# Microcontroller.net
KiCad netlist of a schematic drawn in Altium Designer
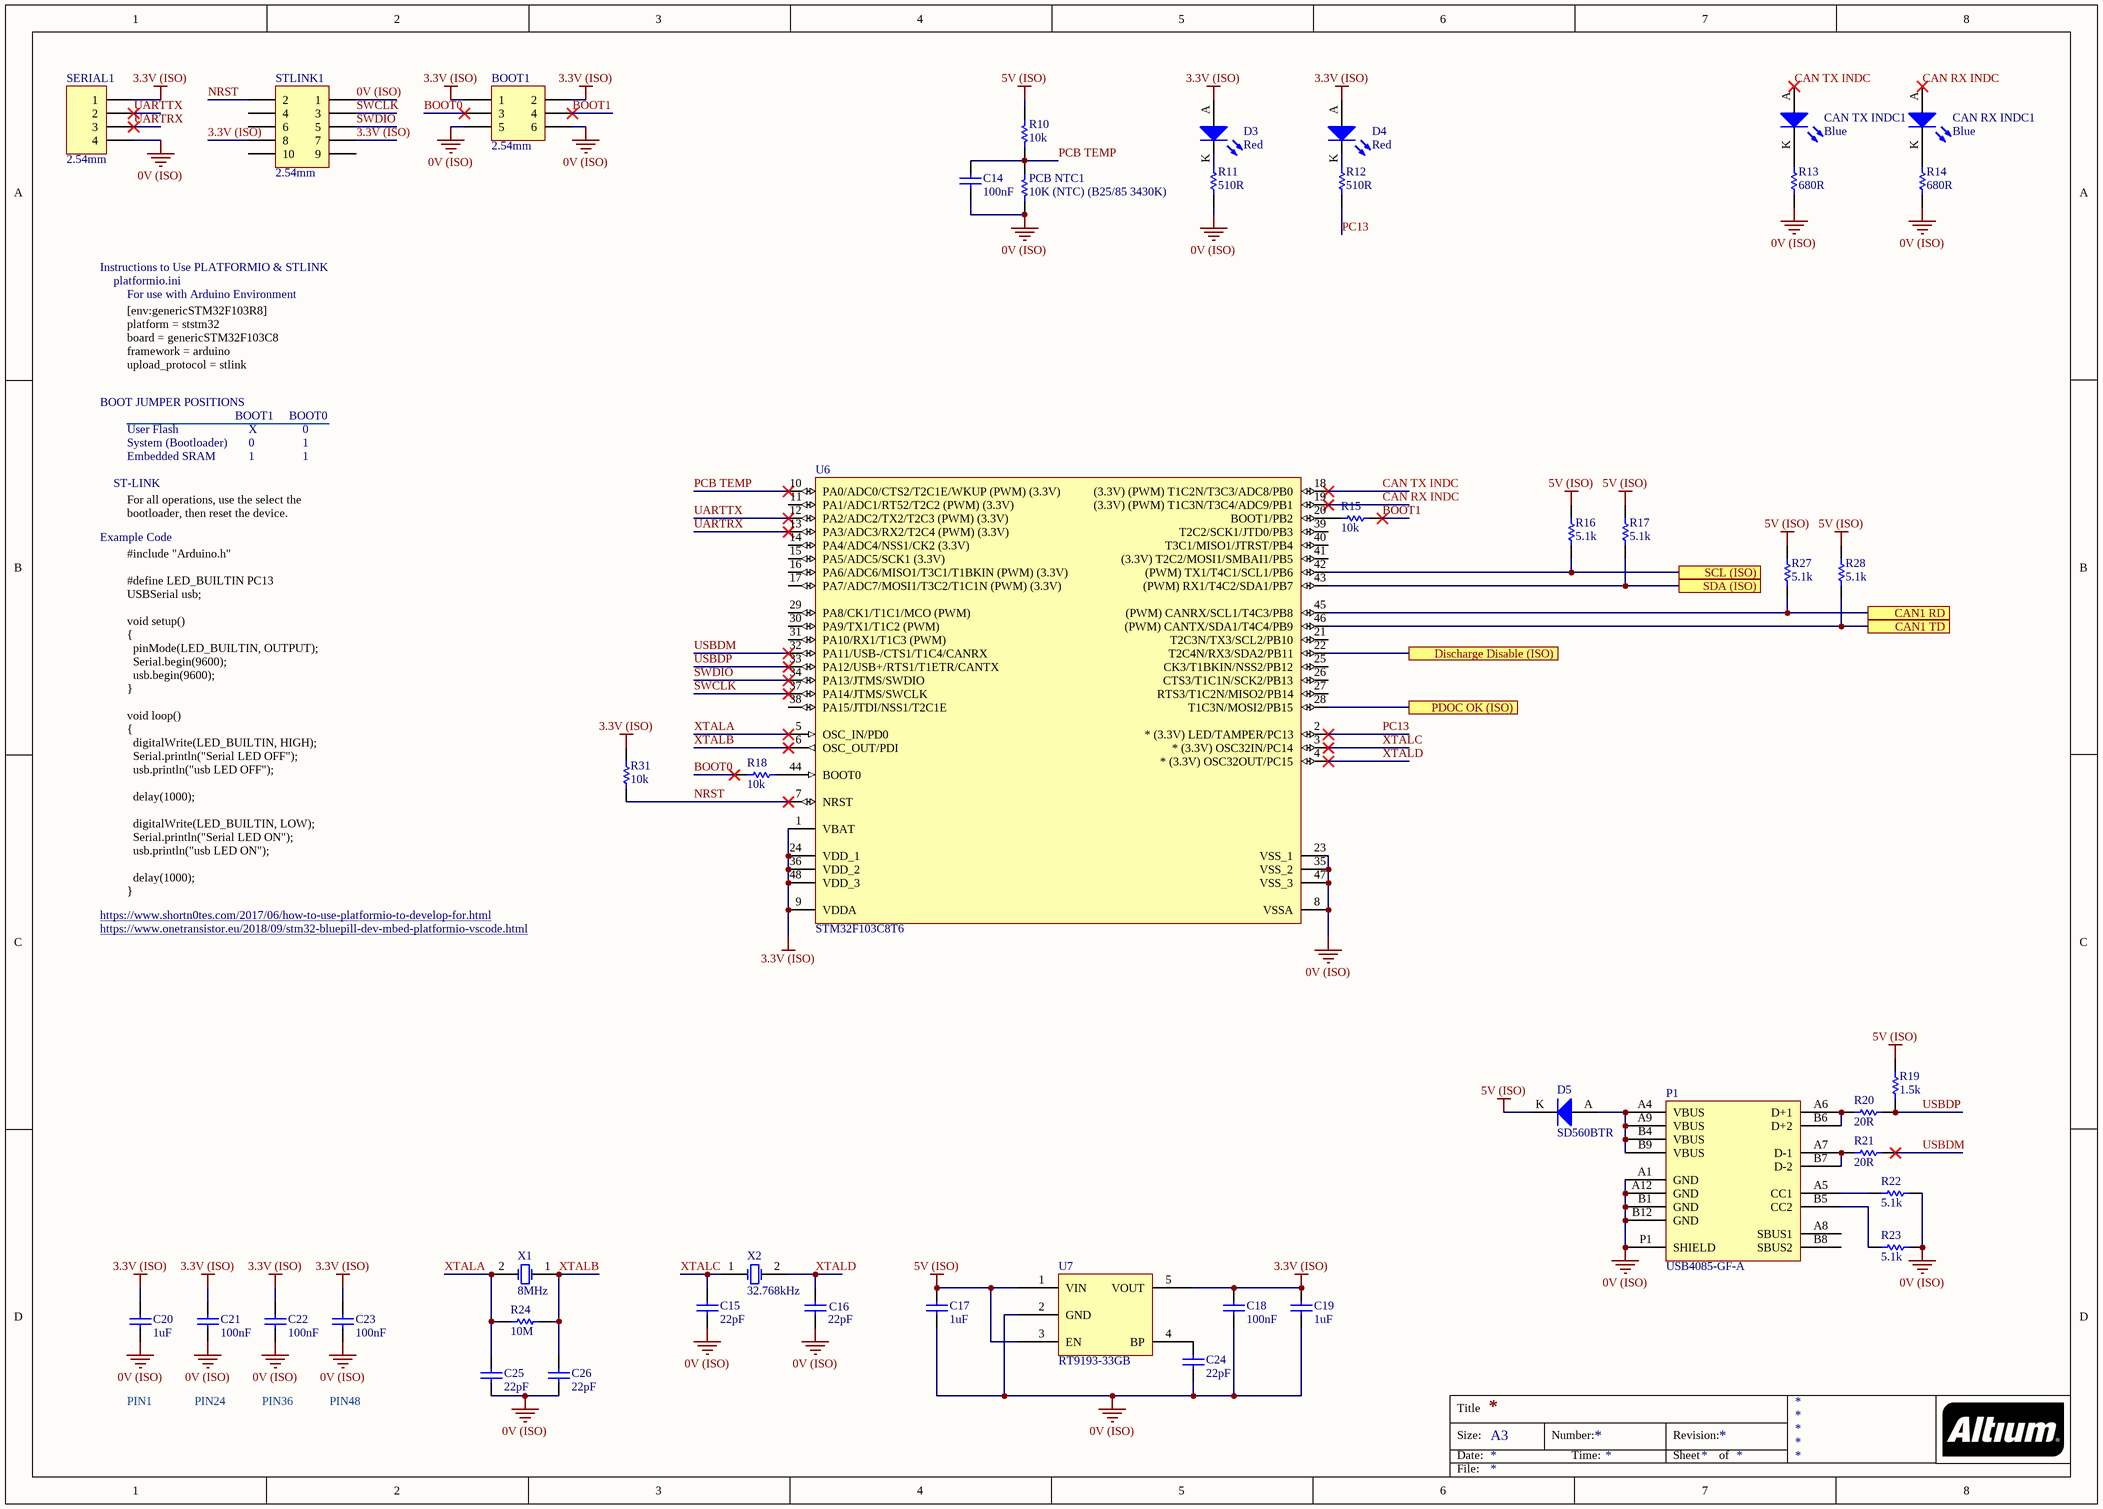
[diagram p0: Microcontroller.SchDoc]

(export (version "E")
  (design (tool "Eeschema 10.0.6"))
  (components
    (comp (ref "BOOT1")
      (value "2.54mm")
      (footprint "TH 2.54mm Header 2x3")
      (fields (field (name "PART NUMBER") "TH 2.54mm Header 2x3") (field (name "CONTACT") "NA"))
      (libsource (lib "ts_20-standard-connectors") (part "Header 2x3"))
    )
    (comp (ref "C14")
      (value "100nF")
      (footprint "0805")
      (fields
        (field (name "PART NUMBER") "GCM21BR71H104KA37L")
        (field (name "TOLERANCE") "±10%")
        (field (name "MANUFACTURER") "muRata")
      )
      (libsource (lib "ts_20-standard-library") (part "Capacitor"))
    )
    (comp (ref "C15")
      (value "22pF")
      (footprint "0805")
      (fields
        (field (name "PART NUMBER") "GRM21A5C2E220JW01D")
        (field (name "TOLERANCE") "±5%")
        (field (name "MANUFACTURER") "muRata")
      )
      (libsource (lib "ts_20-standard-library") (part "Capacitor"))
    )
    (comp (ref "C16")
      (value "22pF")
      (footprint "0805")
      (fields
        (field (name "PART NUMBER") "GRM21A5C2E220JW01D")
        (field (name "TOLERANCE") "±5%")
        (field (name "MANUFACTURER") "muRata")
      )
      (libsource (lib "ts_20-standard-library") (part "Capacitor"))
    )
    (comp (ref "C17")
      (value "1uF")
      (footprint "0805")
      (fields
        (field (name "PART NUMBER") "AC0805KKX7R8BB105")
        (field (name "TOLERANCE") "10%")
        (field (name "MANUFACTURER") "YAGEO")
      )
      (libsource (lib "ts_20-standard-library") (part "Capacitor"))
    )
    (comp (ref "C18")
      (value "100nF")
      (footprint "0805")
      (fields
        (field (name "PART NUMBER") "GCM21BR71H104KA37L")
        (field (name "TOLERANCE") "±10%")
        (field (name "MANUFACTURER") "muRata")
      )
      (libsource (lib "ts_20-standard-library") (part "Capacitor"))
    )
    (comp (ref "C19")
      (value "1uF")
      (footprint "0805")
      (fields
        (field (name "PART NUMBER") "AC0805KKX7R8BB105")
        (field (name "TOLERANCE") "10%")
        (field (name "MANUFACTURER") "YAGEO")
      )
      (libsource (lib "ts_20-standard-library") (part "Capacitor"))
    )
    (comp (ref "C20")
      (value "1uF")
      (footprint "0805")
      (fields
        (field (name "PART NUMBER") "AC0805KKX7R8BB105")
        (field (name "TOLERANCE") "10%")
        (field (name "MANUFACTURER") "YAGEO")
      )
      (libsource (lib "ts_20-standard-library") (part "Capacitor"))
    )
    (comp (ref "C21")
      (value "100nF")
      (footprint "0805")
      (fields
        (field (name "PART NUMBER") "GCM21BR71H104KA37L")
        (field (name "TOLERANCE") "±10%")
        (field (name "MANUFACTURER") "muRata")
      )
      (libsource (lib "ts_20-standard-library") (part "Capacitor"))
    )
    (comp (ref "C22")
      (value "100nF")
      (footprint "0805")
      (fields
        (field (name "PART NUMBER") "GCM21BR71H104KA37L")
        (field (name "TOLERANCE") "±10%")
        (field (name "MANUFACTURER") "muRata")
      )
      (libsource (lib "ts_20-standard-library") (part "Capacitor"))
    )
    (comp (ref "C23")
      (value "100nF")
      (footprint "0805")
      (fields
        (field (name "PART NUMBER") "GCM21BR71H104KA37L")
        (field (name "TOLERANCE") "±10%")
        (field (name "MANUFACTURER") "muRata")
      )
      (libsource (lib "ts_20-standard-library") (part "Capacitor"))
    )
    (comp (ref "C24")
      (value "22pF")
      (footprint "0805")
      (fields
        (field (name "PART NUMBER") "GRM21A5C2E220JW01D")
        (field (name "TOLERANCE") "±5%")
        (field (name "MANUFACTURER") "muRata")
      )
      (libsource (lib "ts_20-standard-library") (part "Capacitor"))
    )
    (comp (ref "C25")
      (value "22pF")
      (footprint "0805")
      (fields
        (field (name "PART NUMBER") "GRM21A5C2E220JW01D")
        (field (name "TOLERANCE") "±5%")
        (field (name "MANUFACTURER") "muRata")
      )
      (libsource (lib "ts_20-standard-library") (part "Capacitor"))
    )
    (comp (ref "C26")
      (value "22pF")
      (footprint "0805")
      (fields
        (field (name "PART NUMBER") "GRM21A5C2E220JW01D")
        (field (name "TOLERANCE") "±5%")
        (field (name "MANUFACTURER") "muRata")
      )
      (libsource (lib "ts_20-standard-library") (part "Capacitor"))
    )
    (comp (ref "CAN RX INDC1")
      (value "Blue")
      (footprint "0805 LED")
      (description "LED BLUE CLEAR 2012 SMD")
      (fields
        (field (name "PART NUMBER") "SML-MN2BCTT86C")
        (field (name "MANUFACTURER") "ROHM Semiconductor")
      )
      (libsource (lib "ts_20-standard-library") (part "LED"))
    )
    (comp (ref "CAN TX INDC1")
      (value "Blue")
      (footprint "0805 LED")
      (description "LED BLUE CLEAR 2012 SMD")
      (fields
        (field (name "PART NUMBER") "SML-MN2BCTT86C")
        (field (name "MANUFACTURER") "ROHM Semiconductor")
      )
      (libsource (lib "ts_20-standard-library") (part "LED"))
    )
    (comp (ref "D3")
      (value "Red")
      (footprint "0805 LED")
      (description "Red LED Indication - Discrete 1.75V 0805 (2012 Metric)")
      (fields (field (name "MANUFACTURER") "ROHM Semiconductor") (field (name "PART NUMBER") "SML-210LTT86"))
      (libsource (lib "ts_20-standard-library") (part "LED"))
    )
    (comp (ref "D4")
      (value "Red")
      (footprint "0805 LED")
      (description "Red LED Indication - Discrete 1.75V 0805 (2012 Metric)")
      (fields (field (name "MANUFACTURER") "ROHM Semiconductor") (field (name "PART NUMBER") "SML-210LTT86"))
      (libsource (lib "ts_20-standard-library") (part "LED"))
    )
    (comp (ref "D5")
      (value "SD560BTR")
      (footprint "SMB Diode")
      (description "1.2V_F 600V 5A SMB")
      (fields
        (field (name "MANUFACTURER") "SMC Diode Solutions")
        (field (name "DIGIKEY PART NUMBER") "1655-1530-2-ND")
      )
      (libsource (lib "ts_20-standard-library") (part "Diode"))
    )
    (comp (ref "P1")
      (value "USB4085-GF-A")
      (footprint "USB4085-GF-A")
      (description "USB - C (Type - C) USB 2.0 Receptacle Connector 16 Position Through Hole, Right Angle")
      (fields (field (name "DIGIKEY PART NUMBER") "2073-USB4085-GF-ACT-ND"))
      (libsource (lib "ts_20-standard-connectors") (part "USB4085-GF-A"))
    )
    (comp (ref "PCB NTC1")
      (value "10K (NTC) (B25/85 3430K)")
      (footprint "0805")
      (fields
        (field (name "PART NUMBER") "NTCS0805E3103FLT")
        (field (name "MANUFACTURER") "Vishay Beyschlag")
        (field (name "TOLERANCE") "0.01")
      )
      (libsource (lib "ts_20-standard-library") (part "Resistor"))
    )
    (comp (ref "R10")
      (value "10k")
      (footprint "0805")
      (fields
        (field (name "PART NUMBER") "RC0805FR0710KL")
        (field (name "MANUFACTURER") "YAGEO")
        (field (name "TOLERANCE") "0.01")
      )
      (libsource (lib "ts_20-standard-library") (part "Resistor"))
    )
    (comp (ref "R11")
      (value "510R")
      (footprint "0805")
      (fields
        (field (name "MANUFACTURER") "YAGEO")
        (field (name "PART NUMBER") "RC0805FR07510RL")
        (field (name "TOLERANCE") "0.01")
      )
      (libsource (lib "ts_20-standard-library") (part "Resistor"))
    )
    (comp (ref "R12")
      (value "510R")
      (footprint "0805")
      (fields
        (field (name "MANUFACTURER") "YAGEO")
        (field (name "PART NUMBER") "RC0805FR07510RL")
        (field (name "TOLERANCE") "0.01")
      )
      (libsource (lib "ts_20-standard-library") (part "Resistor"))
    )
    (comp (ref "R13")
      (value "680R")
      (footprint "0805")
      (fields
        (field (name "PART NUMBER") "RC0805FR07680RL")
        (field (name "MANUFACTURER") "YAGEO")
        (field (name "TOLERANCE") "0.01")
      )
      (libsource (lib "ts_20-standard-library") (part "Resistor"))
    )
    (comp (ref "R14")
      (value "680R")
      (footprint "0805")
      (fields
        (field (name "PART NUMBER") "RC0805FR07680RL")
        (field (name "MANUFACTURER") "YAGEO")
        (field (name "TOLERANCE") "0.01")
      )
      (libsource (lib "ts_20-standard-library") (part "Resistor"))
    )
    (comp (ref "R15")
      (value "10k")
      (footprint "0805")
      (fields
        (field (name "PART NUMBER") "RC0805FR0710KL")
        (field (name "MANUFACTURER") "YAGEO")
        (field (name "TOLERANCE") "0.01")
      )
      (libsource (lib "ts_20-standard-library") (part "Resistor"))
    )
    (comp (ref "R16")
      (value "5.1k")
      (footprint "0805")
      (fields
        (field (name "PART NUMBER") "RC0805FR075K1L")
        (field (name "MANUFACTURER") "YAGEO")
        (field (name "TOLERANCE") "0.01")
      )
      (libsource (lib "ts_20-standard-library") (part "Resistor"))
    )
    (comp (ref "R17")
      (value "5.1k")
      (footprint "0805")
      (fields
        (field (name "PART NUMBER") "RC0805FR075K1L")
        (field (name "MANUFACTURER") "YAGEO")
        (field (name "TOLERANCE") "0.01")
      )
      (libsource (lib "ts_20-standard-library") (part "Resistor"))
    )
    (comp (ref "R18")
      (value "10k")
      (footprint "0805")
      (fields
        (field (name "PART NUMBER") "RC0805FR0710KL")
        (field (name "MANUFACTURER") "YAGEO")
        (field (name "TOLERANCE") "0.01")
      )
      (libsource (lib "ts_20-standard-library") (part "Resistor"))
    )
    (comp (ref "R19")
      (value "1.5k")
      (footprint "0805")
      (fields
        (field (name "PART NUMBER") "RC0805FR071K5L")
        (field (name "MANUFACTURER") "YAGEO")
        (field (name "TOLERANCE") "0.01")
      )
      (libsource (lib "ts_20-standard-library") (part "Resistor"))
    )
    (comp (ref "R20")
      (value "20R")
      (footprint "0805")
      (fields
        (field (name "PART NUMBER") "RC0805FR0720RL")
        (field (name "MANUFACTURER") "YAGEO")
        (field (name "TOLERANCE") "0.01")
      )
      (libsource (lib "ts_20-standard-library") (part "Resistor"))
    )
    (comp (ref "R21")
      (value "20R")
      (footprint "0805")
      (fields
        (field (name "PART NUMBER") "RC0805FR0720RL")
        (field (name "MANUFACTURER") "YAGEO")
        (field (name "TOLERANCE") "0.01")
      )
      (libsource (lib "ts_20-standard-library") (part "Resistor"))
    )
    (comp (ref "R22")
      (value "5.1k")
      (footprint "0805")
      (fields
        (field (name "PART NUMBER") "RC0805FR075K1L")
        (field (name "MANUFACTURER") "YAGEO")
        (field (name "TOLERANCE") "0.01")
      )
      (libsource (lib "ts_20-standard-library") (part "Resistor"))
    )
    (comp (ref "R23")
      (value "5.1k")
      (footprint "0805")
      (fields
        (field (name "PART NUMBER") "RC0805FR075K1L")
        (field (name "MANUFACTURER") "YAGEO")
        (field (name "TOLERANCE") "0.01")
      )
      (libsource (lib "ts_20-standard-library") (part "Resistor"))
    )
    (comp (ref "R24")
      (value "10M")
      (footprint "0805")
      (fields
        (field (name "PART NUMBER") "RC0805FR0710ML")
        (field (name "MANUFACTURER") "YAGEO")
        (field (name "TOLERANCE") "0.01")
      )
      (libsource (lib "ts_20-standard-library") (part "Resistor"))
    )
    (comp (ref "R27")
      (value "5.1k")
      (footprint "0805")
      (fields
        (field (name "PART NUMBER") "RC0805FR075K1L")
        (field (name "MANUFACTURER") "YAGEO")
        (field (name "TOLERANCE") "0.01")
      )
      (libsource (lib "ts_20-standard-library") (part "Resistor"))
    )
    (comp (ref "R28")
      (value "5.1k")
      (footprint "0805")
      (fields
        (field (name "PART NUMBER") "RC0805FR075K1L")
        (field (name "MANUFACTURER") "YAGEO")
        (field (name "TOLERANCE") "0.01")
      )
      (libsource (lib "ts_20-standard-library") (part "Resistor"))
    )
    (comp (ref "R31")
      (value "10k")
      (footprint "0805")
      (fields
        (field (name "PART NUMBER") "RC0805FR0710KL")
        (field (name "MANUFACTURER") "YAGEO")
        (field (name "TOLERANCE") "0.01")
      )
      (libsource (lib "ts_20-standard-library") (part "Resistor"))
    )
    (comp (ref "SERIAL1")
      (value "2.54mm")
      (footprint "TH 2.54mm Header 1x4")
      (fields (field (name "PART NUMBER") "TH 2.54mm Header 1x4") (field (name "CONTACT") "NA"))
      (libsource (lib "ts_20-standard-connectors") (part "Header 1x4"))
    )
    (comp (ref "STLINK1")
      (value "2.54mm")
      (footprint "TH 2.54mm Header 2x5")
      (fields (field (name "PART NUMBER") "TH 2.54mm Header 2x5") (field (name "CONTACT") "NA"))
      (libsource (lib "ts_20-standard-connectors") (part "Header 2x5"))
    )
    (comp (ref "U6")
      (value "STM32F103C8T6")
      (footprint "STM 48-LQFP")
      (description "ARM® Cortex®-M3 STM32F1 Microcontroller IC 32-Bit 72MHz 64KB (64K x 8) FLASH")
      (fields
        (field (name "MANUFACTURER") "STMicroelectronics")
        (field (name "DIGIKEY PART NUMBER") "497-6063-ND")
      )
      (libsource (lib "ts_20-standard-library") (part "STM32F103C8T6"))
    )
    (comp (ref "U7")
      (value "RT9193-33GB")
      (footprint "RICHTEK SOT-23-5")
      (description "IC REG LINEAR 3.3V 300MA SOT23-5")
      (fields (field (name "MANUFACTURER") "Richtek") (field (name "DIGIKEY PART NUMBER") "1028-1014-1-ND"))
      (libsource (lib "ts_20-standard-library") (part "RT9193-33GB"))
    )
    (comp (ref "X1")
      (value "8MHz")
      (footprint "Abracon HC-49/US")
      (fields
        (field (name "PART NUMBER") "ABLS-8.000MHZ-B4-T")
        (field (name "MANUFACTURER") "Abracon LLC")
        (field (name "DIGIKEY PART NUMBER") "535-10212-2-ND")
      )
      (libsource (lib "ts_20-standard-library") (part "Crystal"))
    )
    (comp (ref "X2")
      (value "32.768kHz")
      (footprint "EPSON 2-SMD")
      (fields
        (field (name "PART NUMBER") "FC-135 32.7680KA-A5")
        (field (name "MANUFACTURER") "EPSON")
        (field (name "DIGIKEY PART NUMBER") "SER4103TR-ND")
      )
      (libsource (lib "ts_20-standard-library") (part "Crystal"))
    )
  )
  (nets
    (net (code "1") (name "/BOOT0") (class "Default")
      (node (ref "BOOT1") (pin "3") (pinfunction "3_3") (pintype "passive"))
      (node (ref "R18") (pin "1") (pinfunction "1_1") (pintype "passive"))
    )
    (net (code "2") (name "/BOOT1") (class "Default")
      (node (ref "BOOT1") (pin "4") (pinfunction "4_4") (pintype "passive"))
      (node (ref "R15") (pin "2") (pinfunction "2_2") (pintype "passive"))
    )
    (net (code "3") (name "/CAN RX INDC") (class "Default")
      (node (ref "CAN RX INDC1") (pin "A") (pinfunction "A_A") (pintype "passive"))
      (node (ref "U6") (pin "19") (pinfunction "(3.3V)_(PWM)_T1C3N/T3C4/ADC9/PB1_19") (pintype "bidirectional"))
    )
    (net (code "4") (name "/CAN TX INDC") (class "Default")
      (node (ref "CAN TX INDC1") (pin "A") (pinfunction "A_A") (pintype "passive"))
      (node (ref "U6") (pin "18") (pinfunction "(3.3V)_(PWM)_T1C2N/T3C3/ADC8/PB0_18") (pintype "bidirectional"))
    )
    (net (code "5") (name "/CAN1 RD") (class "Default")
      (node (ref "R27") (pin "1") (pinfunction "1_1") (pintype "passive"))
      (node (ref "U6") (pin "45") (pinfunction "(PWM)_CANRX/SCL1/T4C3/PB8_45") (pintype "bidirectional"))
    )
    (net (code "6") (name "/CAN1 TD") (class "Default")
      (node (ref "R28") (pin "1") (pinfunction "1_1") (pintype "passive"))
      (node (ref "U6") (pin "46") (pinfunction "(PWM)_CANTX/SDA1/T4C4/PB9_46") (pintype "bidirectional"))
    )
    (net (code "7") (name "/Discharge Disable (ISO)") (class "Default")
      (node (ref "U6") (pin "22") (pinfunction "T2C4N/RX3/SDA2/PB11_22") (pintype "bidirectional"))
    )
    (net (code "8") (name "/NRST") (class "Default")
      (node (ref "R31") (pin "1") (pinfunction "1_1") (pintype "passive"))
      (node (ref "STLINK1") (pin "2") (pinfunction "2_2") (pintype "passive"))
      (node (ref "U6") (pin "7") (pinfunction "NRST_7") (pintype "bidirectional"))
    )
    (net (code "9") (name "/PC13") (class "Default")
      (node (ref "R12") (pin "1") (pinfunction "1_1") (pintype "passive"))
      (node (ref "U6") (pin "2") (pinfunction "*_(3.3V)_LED/TAMPER/PC13_2") (pintype "bidirectional"))
    )
    (net (code "10") (name "/PCB TEMP") (class "Default")
      (node (ref "C14") (pin "2") (pinfunction "2_2") (pintype "passive"))
      (node (ref "PCB NTC1") (pin "2") (pinfunction "2_2") (pintype "passive"))
      (node (ref "R10") (pin "1") (pinfunction "1_1") (pintype "passive"))
      (node (ref "U6") (pin "10") (pinfunction "PA0/ADC0/CTS2/T2C1E/WKUP_(PWM)_(3.3V)_10") (pintype "bidirectional"))
    )
    (net (code "11") (name "/PDOC OK (ISO)") (class "Default")
      (node (ref "U6") (pin "28") (pinfunction "T1C3N/MOSI2/PB15_28") (pintype "bidirectional"))
    )
    (net (code "12") (name "/SCL (ISO)") (class "Default")
      (node (ref "R16") (pin "1") (pinfunction "1_1") (pintype "passive"))
      (node (ref "U6") (pin "42") (pinfunction "(PWM)_TX1/T4C1/SCL1/PB6_42") (pintype "bidirectional"))
    )
    (net (code "13") (name "/SDA (ISO)") (class "Default")
      (node (ref "R17") (pin "1") (pinfunction "1_1") (pintype "passive"))
      (node (ref "U6") (pin "43") (pinfunction "(PWM)_RX1/T4C2/SDA1/PB7_43") (pintype "bidirectional"))
    )
    (net (code "14") (name "/SWCLK") (class "Default")
      (node (ref "STLINK1") (pin "3") (pinfunction "3_3") (pintype "passive"))
      (node (ref "U6") (pin "37") (pinfunction "PA14/JTMS/SWCLK_37") (pintype "bidirectional"))
    )
    (net (code "15") (name "/SWDIO") (class "Default")
      (node (ref "STLINK1") (pin "5") (pinfunction "5_5") (pintype "passive"))
      (node (ref "U6") (pin "34") (pinfunction "PA13/JTMS/SWDIO_34") (pintype "bidirectional"))
    )
    (net (code "16") (name "/UARTRX") (class "Default")
      (node (ref "SERIAL1") (pin "3") (pinfunction "3_3") (pintype "passive"))
      (node (ref "U6") (pin "13") (pinfunction "PA3/ADC3/RX2/T2C4_(PWM)_(3.3V)_13") (pintype "bidirectional"))
    )
    (net (code "17") (name "/UARTTX") (class "Default")
      (node (ref "SERIAL1") (pin "2") (pinfunction "2_2") (pintype "passive"))
      (node (ref "U6") (pin "12") (pinfunction "PA2/ADC2/TX2/T2C3_(PWM)_(3.3V)_12") (pintype "bidirectional"))
    )
    (net (code "18") (name "/USBDM") (class "Default")
      (node (ref "R21") (pin "2") (pinfunction "2_2") (pintype "passive"))
      (node (ref "U6") (pin "32") (pinfunction "PA11/USB-/CTS1/T1C4/CANRX_32") (pintype "bidirectional"))
    )
    (net (code "19") (name "/USBDP") (class "Default")
      (node (ref "R19") (pin "1") (pinfunction "1_1") (pintype "passive"))
      (node (ref "R20") (pin "2") (pinfunction "2_2") (pintype "passive"))
      (node (ref "U6") (pin "33") (pinfunction "PA12/USB+/RTS1/T1ETR/CANTX_33") (pintype "bidirectional"))
    )
    (net (code "20") (name "/XTALA") (class "Default")
      (node (ref "C25") (pin "2") (pinfunction "2_2") (pintype "passive"))
      (node (ref "R24") (pin "2") (pinfunction "2_2") (pintype "passive"))
      (node (ref "U6") (pin "5") (pinfunction "OSC_IN/PD0_5") (pintype "input"))
      (node (ref "X1") (pin "2") (pinfunction "OSC2_2") (pintype "passive"))
    )
    (net (code "21") (name "/XTALB") (class "Default")
      (node (ref "C26") (pin "2") (pinfunction "2_2") (pintype "passive"))
      (node (ref "R24") (pin "1") (pinfunction "1_1") (pintype "passive"))
      (node (ref "U6") (pin "6") (pinfunction "OSC_OUT/PDI_6") (pintype "output"))
      (node (ref "X1") (pin "1") (pinfunction "OSC1_1") (pintype "passive"))
    )
    (net (code "22") (name "/XTALC") (class "Default")
      (node (ref "C15") (pin "2") (pinfunction "2_2") (pintype "passive"))
      (node (ref "U6") (pin "3") (pinfunction "*_(3.3V)_OSC32IN/PC14_3") (pintype "bidirectional"))
      (node (ref "X2") (pin "1") (pinfunction "OSC1_1") (pintype "passive"))
    )
    (net (code "23") (name "/XTALD") (class "Default")
      (node (ref "C16") (pin "2") (pinfunction "2_2") (pintype "passive"))
      (node (ref "U6") (pin "4") (pinfunction "*_(3.3V)_OSC32OUT/PC15_4") (pintype "bidirectional"))
      (node (ref "X2") (pin "2") (pinfunction "OSC2_2") (pintype "passive"))
    )
    (net (code "24") (name "0V (ISO)") (class "Default")
      (node (ref "BOOT1") (pin "5") (pinfunction "5_5") (pintype "passive"))
      (node (ref "BOOT1") (pin "6") (pinfunction "6_6") (pintype "passive"))
      (node (ref "C14") (pin "1") (pinfunction "1_1") (pintype "passive"))
      (node (ref "C15") (pin "1") (pinfunction "1_1") (pintype "passive"))
      (node (ref "C16") (pin "1") (pinfunction "1_1") (pintype "passive"))
      (node (ref "C17") (pin "1") (pinfunction "1_1") (pintype "passive"))
      (node (ref "C18") (pin "1") (pinfunction "1_1") (pintype "passive"))
      (node (ref "C19") (pin "1") (pinfunction "1_1") (pintype "passive"))
      (node (ref "C20") (pin "1") (pinfunction "1_1") (pintype "passive"))
      (node (ref "C21") (pin "1") (pinfunction "1_1") (pintype "passive"))
      (node (ref "C22") (pin "1") (pinfunction "1_1") (pintype "passive"))
      (node (ref "C23") (pin "1") (pinfunction "1_1") (pintype "passive"))
      (node (ref "C24") (pin "1") (pinfunction "1_1") (pintype "passive"))
      (node (ref "C25") (pin "1") (pinfunction "1_1") (pintype "passive"))
      (node (ref "C26") (pin "1") (pinfunction "1_1") (pintype "passive"))
      (node (ref "P1") (pin "A1") (pinfunction "GND_A1") (pintype "passive"))
      (node (ref "P1") (pin "A12") (pinfunction "GND_A12") (pintype "passive"))
      (node (ref "P1") (pin "B1") (pinfunction "GND_B1") (pintype "passive"))
      (node (ref "P1") (pin "B12") (pinfunction "GND_B12") (pintype "passive"))
      (node (ref "P1") (pin "P1") (pinfunction "SHIELD_P1") (pintype "passive"))
      (node (ref "PCB NTC1") (pin "1") (pinfunction "1_1") (pintype "passive"))
      (node (ref "R11") (pin "1") (pinfunction "1_1") (pintype "passive"))
      (node (ref "R13") (pin "1") (pinfunction "1_1") (pintype "passive"))
      (node (ref "R14") (pin "1") (pinfunction "1_1") (pintype "passive"))
      (node (ref "R22") (pin "2") (pinfunction "2_2") (pintype "passive"))
      (node (ref "R23") (pin "2") (pinfunction "2_2") (pintype "passive"))
      (node (ref "SERIAL1") (pin "4") (pinfunction "4_4") (pintype "passive"))
      (node (ref "STLINK1") (pin "1") (pinfunction "1_1") (pintype "passive"))
      (node (ref "U6") (pin "23") (pinfunction "VSS_1_23") (pintype "power_in"))
      (node (ref "U6") (pin "35") (pinfunction "VSS_2_35") (pintype "power_in"))
      (node (ref "U6") (pin "47") (pinfunction "VSS_3_47") (pintype "power_in"))
      (node (ref "U6") (pin "8") (pinfunction "VSSA_8") (pintype "power_in"))
      (node (ref "U7") (pin "2") (pinfunction "GND_2") (pintype "passive"))
    )
    (net (code "25") (name "3.3V (ISO)") (class "Default")
      (node (ref "BOOT1") (pin "1") (pinfunction "1_1") (pintype "passive"))
      (node (ref "BOOT1") (pin "2") (pinfunction "2_2") (pintype "passive"))
      (node (ref "C18") (pin "2") (pinfunction "2_2") (pintype "passive"))
      (node (ref "C19") (pin "2") (pinfunction "2_2") (pintype "passive"))
      (node (ref "C20") (pin "2") (pinfunction "2_2") (pintype "passive"))
      (node (ref "C21") (pin "2") (pinfunction "2_2") (pintype "passive"))
      (node (ref "C22") (pin "2") (pinfunction "2_2") (pintype "passive"))
      (node (ref "C23") (pin "2") (pinfunction "2_2") (pintype "passive"))
      (node (ref "D3") (pin "A") (pinfunction "A_A") (pintype "passive"))
      (node (ref "D4") (pin "A") (pinfunction "A_A") (pintype "passive"))
      (node (ref "R31") (pin "2") (pinfunction "2_2") (pintype "passive"))
      (node (ref "SERIAL1") (pin "1") (pinfunction "1_1") (pintype "passive"))
      (node (ref "STLINK1") (pin "7") (pinfunction "7_7") (pintype "passive"))
      (node (ref "STLINK1") (pin "8") (pinfunction "8_8") (pintype "passive"))
      (node (ref "U6") (pin "1") (pinfunction "VBAT_1") (pintype "power_in"))
      (node (ref "U6") (pin "24") (pinfunction "VDD_1_24") (pintype "power_in"))
      (node (ref "U6") (pin "36") (pinfunction "VDD_2_36") (pintype "power_in"))
      (node (ref "U6") (pin "48") (pinfunction "VDD_3_48") (pintype "power_in"))
      (node (ref "U6") (pin "9") (pinfunction "VDDA_9") (pintype "power_in"))
      (node (ref "U7") (pin "5") (pinfunction "VOUT_5") (pintype "passive"))
    )
    (net (code "26") (name "5V (ISO)") (class "Default")
      (node (ref "C17") (pin "2") (pinfunction "2_2") (pintype "passive"))
      (node (ref "D5") (pin "K") (pinfunction "K_K") (pintype "passive"))
      (node (ref "R10") (pin "2") (pinfunction "2_2") (pintype "passive"))
      (node (ref "R16") (pin "2") (pinfunction "2_2") (pintype "passive"))
      (node (ref "R17") (pin "2") (pinfunction "2_2") (pintype "passive"))
      (node (ref "R19") (pin "2") (pinfunction "2_2") (pintype "passive"))
      (node (ref "R27") (pin "2") (pinfunction "2_2") (pintype "passive"))
      (node (ref "R28") (pin "2") (pinfunction "2_2") (pintype "passive"))
      (node (ref "U7") (pin "1") (pinfunction "VIN_1") (pintype "passive"))
      (node (ref "U7") (pin "3") (pinfunction "EN_3") (pintype "passive"))
    )
    (net (code "27") (name "Net-(CAN RX INDC1-PadK)") (class "Default")
      (node (ref "CAN RX INDC1") (pin "K") (pinfunction "K_K") (pintype "passive"))
      (node (ref "R14") (pin "2") (pinfunction "2_2") (pintype "passive"))
    )
    (net (code "28") (name "Net-(CAN TX INDC1-PadK)") (class "Default")
      (node (ref "CAN TX INDC1") (pin "K") (pinfunction "K_K") (pintype "passive"))
      (node (ref "R13") (pin "2") (pinfunction "2_2") (pintype "passive"))
    )
    (net (code "29") (name "Net-(D3-PadK)") (class "Default")
      (node (ref "D3") (pin "K") (pinfunction "K_K") (pintype "passive"))
      (node (ref "R11") (pin "2") (pinfunction "2_2") (pintype "passive"))
    )
    (net (code "30") (name "Net-(D4-PadK)") (class "Default")
      (node (ref "D4") (pin "K") (pinfunction "K_K") (pintype "passive"))
      (node (ref "R12") (pin "2") (pinfunction "2_2") (pintype "passive"))
    )
    (net (code "31") (name "Net-(D5-PadA)") (class "Default")
      (node (ref "D5") (pin "A") (pinfunction "A_A") (pintype "passive"))
      (node (ref "P1") (pin "A4") (pinfunction "VBUS_A4") (pintype "passive"))
      (node (ref "P1") (pin "A9") (pinfunction "VBUS_A9") (pintype "passive"))
      (node (ref "P1") (pin "B4") (pinfunction "VBUS_B4") (pintype "passive"))
      (node (ref "P1") (pin "B9") (pinfunction "VBUS_B9") (pintype "passive"))
    )
    (net (code "32") (name "Net-(P1-CC1)") (class "Default")
      (node (ref "P1") (pin "A5") (pinfunction "CC1_A5") (pintype "passive"))
      (node (ref "R22") (pin "1") (pinfunction "1_1") (pintype "passive"))
    )
    (net (code "33") (name "Net-(P1-CC2)") (class "Default")
      (node (ref "P1") (pin "B5") (pinfunction "CC2_B5") (pintype "passive"))
      (node (ref "R23") (pin "1") (pinfunction "1_1") (pintype "passive"))
    )
    (net (code "34") (name "Net-(P1-D+1)") (class "Default")
      (node (ref "P1") (pin "A6") (pinfunction "D+1_A6") (pintype "passive"))
      (node (ref "P1") (pin "B6") (pinfunction "D+2_B6") (pintype "passive"))
      (node (ref "R20") (pin "1") (pinfunction "1_1") (pintype "passive"))
    )
    (net (code "35") (name "Net-(P1-D-1)") (class "Default")
      (node (ref "P1") (pin "A7") (pinfunction "D-1_A7") (pintype "passive"))
      (node (ref "P1") (pin "B7") (pinfunction "D-2_B7") (pintype "passive"))
      (node (ref "R21") (pin "1") (pinfunction "1_1") (pintype "passive"))
    )
    (net (code "36") (name "Net-(U6-BOOT0)") (class "Default")
      (node (ref "R18") (pin "2") (pinfunction "2_2") (pintype "passive"))
      (node (ref "U6") (pin "44") (pinfunction "BOOT0_44") (pintype "input"))
    )
    (net (code "37") (name "Net-(U6-BOOT1{slash}PB2)") (class "Default")
      (node (ref "R15") (pin "1") (pinfunction "1_1") (pintype "passive"))
      (node (ref "U6") (pin "20") (pinfunction "BOOT1/PB2_20") (pintype "bidirectional"))
    )
    (net (code "38") (name "Net-(U7-BP)") (class "Default")
      (node (ref "C24") (pin "2") (pinfunction "2_2") (pintype "passive"))
      (node (ref "U7") (pin "4") (pinfunction "BP_4") (pintype "passive"))
    )
    (net (code "39") (name "unconnected-(P1-SBUS1-PadA8)") (class "Default")
      (node (ref "P1") (pin "A8") (pinfunction "SBUS1_A8") (pintype "passive"))
    )
    (net (code "40") (name "unconnected-(P1-SBUS2-PadB8)") (class "Default")
      (node (ref "P1") (pin "B8") (pinfunction "SBUS2_B8") (pintype "passive"))
    )
    (net (code "41") (name "unconnected-(STLINK1-Pad4)") (class "Default")
      (node (ref "STLINK1") (pin "4") (pinfunction "4_4") (pintype "passive"))
    )
    (net (code "42") (name "unconnected-(STLINK1-Pad6)") (class "Default")
      (node (ref "STLINK1") (pin "6") (pinfunction "6_6") (pintype "passive"))
    )
    (net (code "43") (name "unconnected-(STLINK1-Pad9)") (class "Default")
      (node (ref "STLINK1") (pin "9") (pinfunction "9_9") (pintype "passive"))
    )
    (net (code "44") (name "unconnected-(STLINK1-Pad10)") (class "Default")
      (node (ref "STLINK1") (pin "10") (pinfunction "10_10") (pintype "passive"))
    )
    (net (code "45") (name "unconnected-(U6-(3.3V)_T2C2{slash}MOSI1{slash}SMBAI1{slash}PB5-Pad41)") (class "Default")
      (node (ref "U6") (pin "41") (pinfunction "(3.3V)_T2C2/MOSI1/SMBAI1/PB5_41") (pintype "bidirectional"))
    )
    (net (code "46") (name "unconnected-(U6-CK3{slash}T1BKIN{slash}NSS2{slash}PB12-Pad25)") (class "Default")
      (node (ref "U6") (pin "25") (pinfunction "CK3/T1BKIN/NSS2/PB12_25") (pintype "bidirectional"))
    )
    (net (code "47") (name "unconnected-(U6-CTS3{slash}T1C1N{slash}SCK2{slash}PB13-Pad26)") (class "Default")
      (node (ref "U6") (pin "26") (pinfunction "CTS3/T1C1N/SCK2/PB13_26") (pintype "bidirectional"))
    )
    (net (code "48") (name "unconnected-(U6-PA1{slash}ADC1{slash}RT52{slash}T2C2_(PWM)_(3.3V)-Pad11)") (class "Default")
      (node (ref "U6") (pin "11") (pinfunction "PA1/ADC1/RT52/T2C2_(PWM)_(3.3V)_11") (pintype "bidirectional"))
    )
    (net (code "49") (name "unconnected-(U6-PA4{slash}ADC4{slash}NSS1{slash}CK2_(3.3V)-Pad14)") (class "Default")
      (node (ref "U6") (pin "14") (pinfunction "PA4/ADC4/NSS1/CK2_(3.3V)_14") (pintype "bidirectional"))
    )
    (net (code "50") (name "unconnected-(U6-PA5{slash}ADC5{slash}SCK1_(3.3V)-Pad15)") (class "Default")
      (node (ref "U6") (pin "15") (pinfunction "PA5/ADC5/SCK1_(3.3V)_15") (pintype "bidirectional"))
    )
    (net (code "51") (name "unconnected-(U6-PA6{slash}ADC6{slash}MISO1{slash}T3C1{slash}T1BKIN_(PWM)_(3.3V)-Pad16)") (class "Default")
      (node (ref "U6") (pin "16") (pinfunction "PA6/ADC6/MISO1/T3C1/T1BKIN_(PWM)_(3.3V)_16") (pintype "bidirectional"))
    )
    (net (code "52") (name "unconnected-(U6-PA7{slash}ADC7{slash}MOSI1{slash}T3C2{slash}T1C1N_(PWM)_(3.3V)-Pad17)") (class "Default")
      (node (ref "U6") (pin "17") (pinfunction "PA7/ADC7/MOSI1/T3C2/T1C1N_(PWM)_(3.3V)_17") (pintype "bidirectional"))
    )
    (net (code "53") (name "unconnected-(U6-PA8{slash}CK1{slash}T1C1{slash}MCO_(PWM)-Pad29)") (class "Default")
      (node (ref "U6") (pin "29") (pinfunction "PA8/CK1/T1C1/MCO_(PWM)_29") (pintype "bidirectional"))
    )
    (net (code "54") (name "unconnected-(U6-PA9{slash}TX1{slash}T1C2_(PWM)-Pad30)") (class "Default")
      (node (ref "U6") (pin "30") (pinfunction "PA9/TX1/T1C2_(PWM)_30") (pintype "bidirectional"))
    )
    (net (code "55") (name "unconnected-(U6-PA10{slash}RX1{slash}T1C3_(PWM)-Pad31)") (class "Default")
      (node (ref "U6") (pin "31") (pinfunction "PA10/RX1/T1C3_(PWM)_31") (pintype "bidirectional"))
    )
    (net (code "56") (name "unconnected-(U6-PA15{slash}JTDI{slash}NSS1{slash}T2C1E-Pad38)") (class "Default")
      (node (ref "U6") (pin "38") (pinfunction "PA15/JTDI/NSS1/T2C1E_38") (pintype "bidirectional"))
    )
    (net (code "57") (name "unconnected-(U6-RTS3{slash}T1C2N{slash}MISO2{slash}PB14-Pad27)") (class "Default")
      (node (ref "U6") (pin "27") (pinfunction "RTS3/T1C2N/MISO2/PB14_27") (pintype "bidirectional"))
    )
    (net (code "58") (name "unconnected-(U6-T2C2{slash}SCK1{slash}JTD0{slash}PB3-Pad39)") (class "Default")
      (node (ref "U6") (pin "39") (pinfunction "T2C2/SCK1/JTD0/PB3_39") (pintype "bidirectional"))
    )
    (net (code "59") (name "unconnected-(U6-T2C3N{slash}TX3{slash}SCL2{slash}PB10-Pad21)") (class "Default")
      (node (ref "U6") (pin "21") (pinfunction "T2C3N/TX3/SCL2/PB10_21") (pintype "bidirectional"))
    )
    (net (code "60") (name "unconnected-(U6-T3C1{slash}MISO1{slash}JTRST{slash}PB4-Pad40)") (class "Default")
      (node (ref "U6") (pin "40") (pinfunction "T3C1/MISO1/JTRST/PB4_40") (pintype "bidirectional"))
    )
  )
)
